# motorServoDriver.net
KiCad netlist of a schematic drawn in Altium Designer
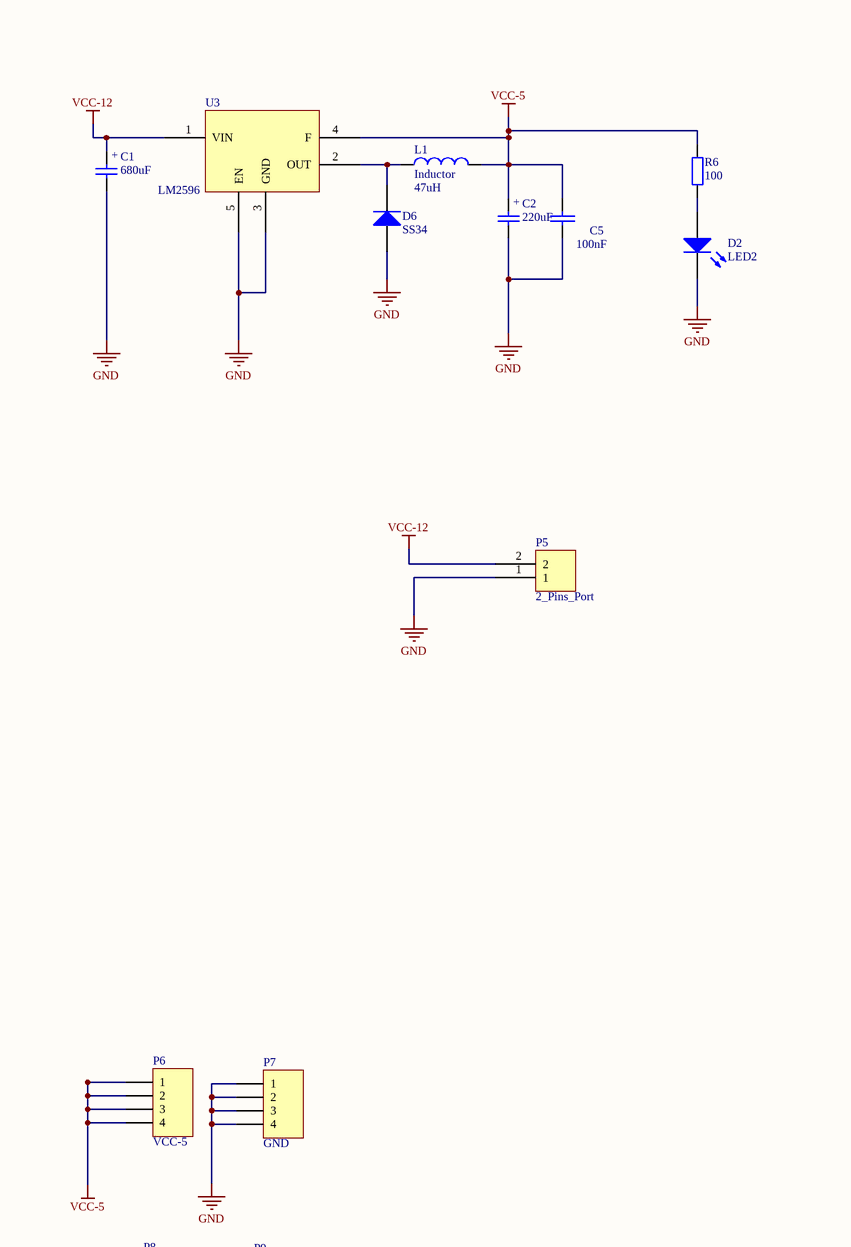
[diagram p0: motorServoDriver.SchDoc, top left]
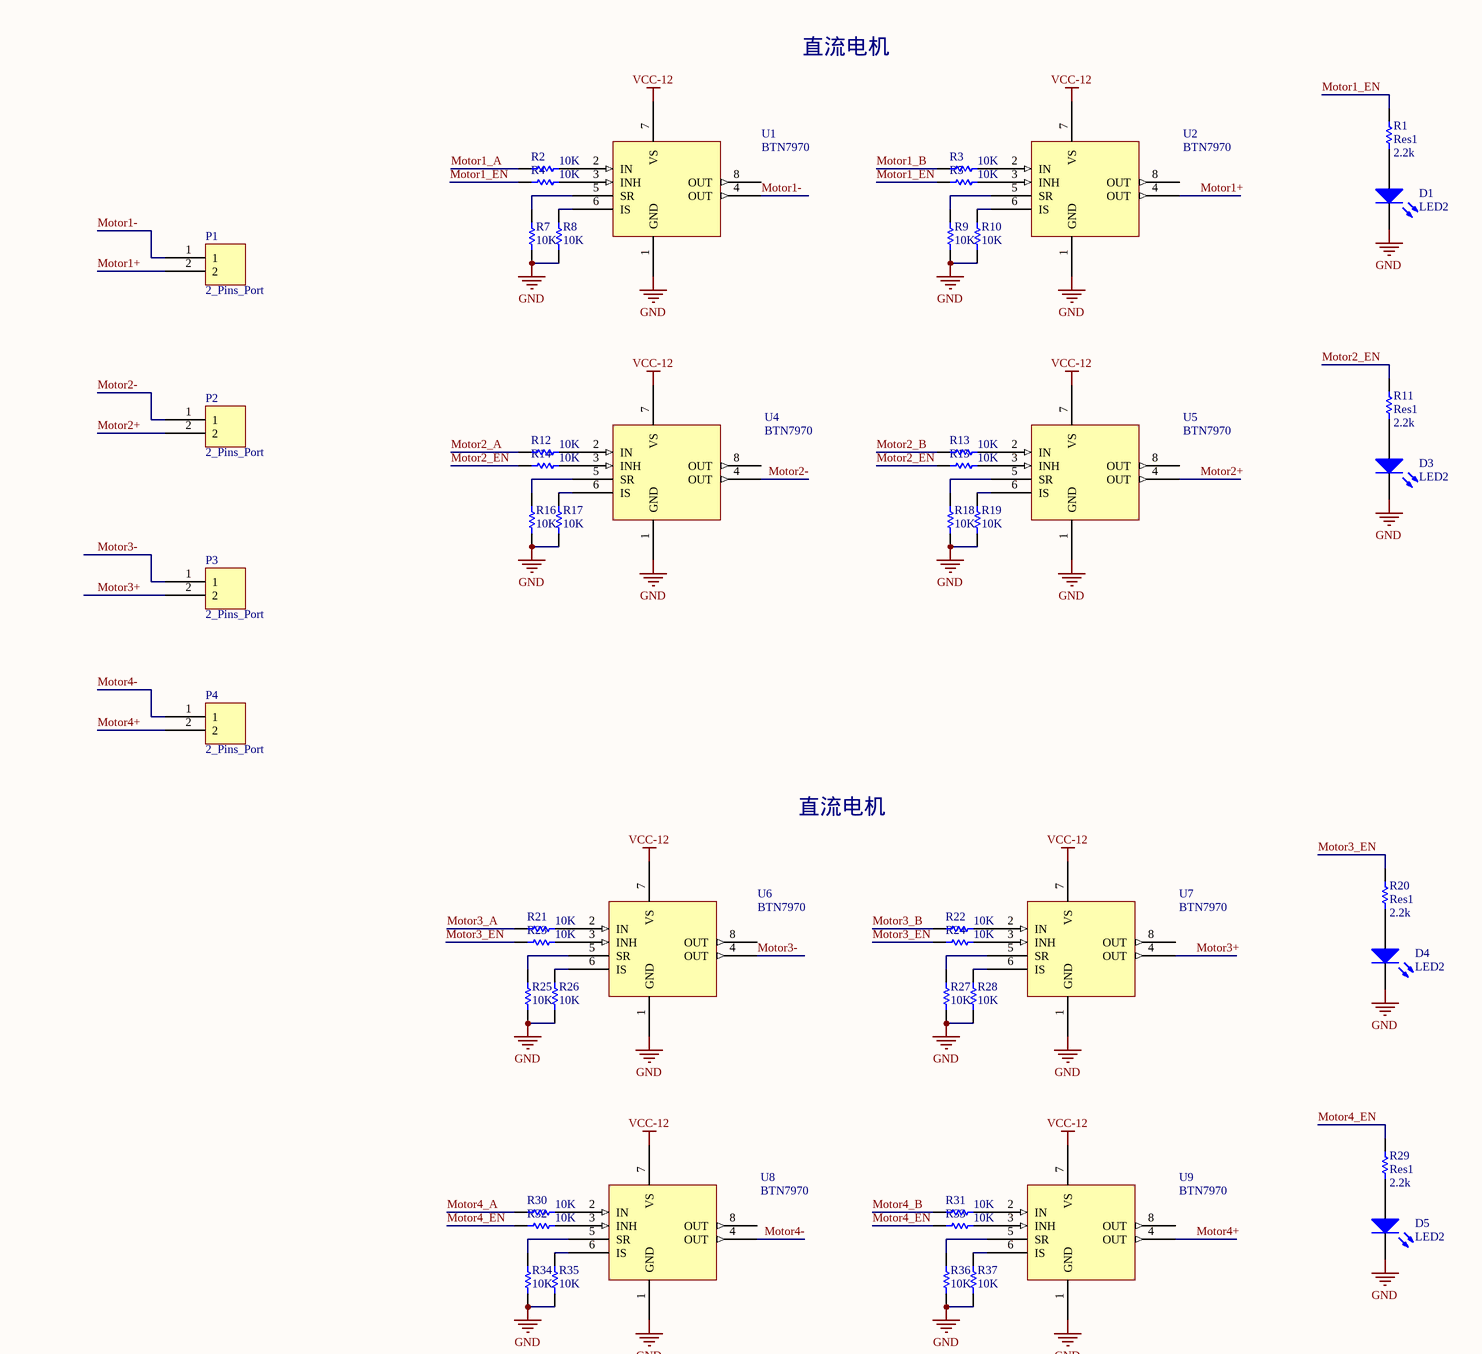
[diagram p1: motorServoDriver.SchDoc, top right]
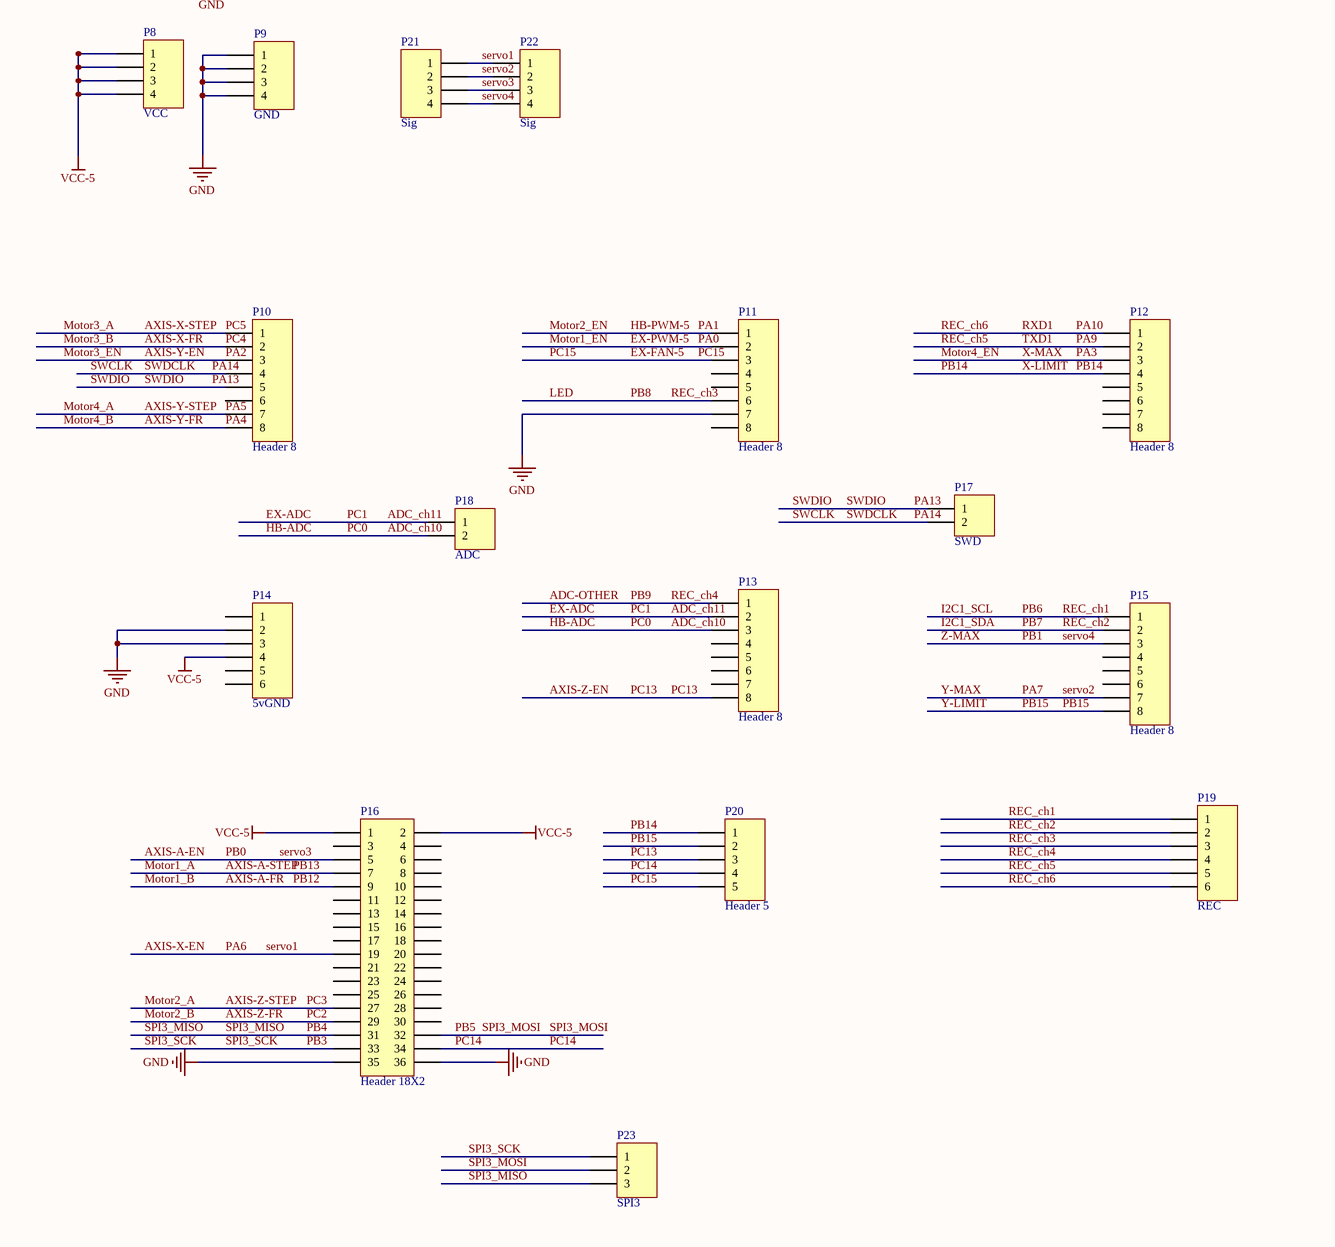
[diagram p2: motorServoDriver.SchDoc, bottom left]

(export (version "E")
  (design (tool "Eeschema 10.0.6"))
  (components
    (comp (ref "C1")
      (value "680uF")
      (footprint "CAP-7343")
      (description "贴片极性电容")
      (fields (field (name "Comment") "Cap"))
      (libsource (lib "SkyWorks2") (part "Cap Pol S"))
    )
    (comp (ref "C2")
      (value "220uF")
      (footprint "CAP-7343")
      (description "贴片极性电容")
      (fields (field (name "Comment") "Cap"))
      (libsource (lib "SkyWorks2") (part "Cap Pol S"))
    )
    (comp (ref "C5")
      (value "100nF")
      (footprint "CAP-0603")
      (description "贴片无极性电容")
      (fields (field (name "Comment") "cap smd"))
      (libsource (lib "SkyWorks2") (part "CAP"))
    )
    (comp (ref "D1")
      (value "LED2")
      (footprint "D2012[0805]")
      (description "Typical RED, GREEN, YELLOW, AMBER GaAs LED")
      (fields (field (name "PUBLISHER") "Altium Limited"))
      (libsource (lib "Miscellaneous Devices") (part "LED2"))
    )
    (comp (ref "D2")
      (value "LED2")
      (footprint "D2012[0805]")
      (description "Typical RED, GREEN, YELLOW, AMBER GaAs LED")
      (fields (field (name "PUBLISHER") "Altium Limited"))
      (libsource (lib "SkyWorks2") (part "LED2"))
    )
    (comp (ref "D3")
      (value "LED2")
      (footprint "D2012[0805]")
      (description "Typical RED, GREEN, YELLOW, AMBER GaAs LED")
      (fields (field (name "PUBLISHER") "Altium Limited"))
      (libsource (lib "Miscellaneous Devices") (part "LED2"))
    )
    (comp (ref "D4")
      (value "LED2")
      (footprint "D2012[0805]")
      (description "Typical RED, GREEN, YELLOW, AMBER GaAs LED")
      (fields (field (name "PUBLISHER") "Altium Limited"))
      (libsource (lib "Miscellaneous Devices") (part "LED2"))
    )
    (comp (ref "D5")
      (value "LED2")
      (footprint "D2012[0805]")
      (description "Typical RED, GREEN, YELLOW, AMBER GaAs LED")
      (fields (field (name "PUBLISHER") "Altium Limited"))
      (libsource (lib "Miscellaneous Devices") (part "LED2"))
    )
    (comp (ref "D6")
      (value "SS34")
      (footprint "LC-SMB(DO-214AA)_S3")
      (description "3 Amp General Purpose Rectifier")
      (fields (field (name "PUBLISHER") "Altium Limited"))
      (libsource (lib "Miscellaneous Devices") (part "Diode 1N5400"))
    )
    (comp (ref "L1")
      (value "Inductor")
      (footprint "Inductor1207")
      (fields (field (name "ALTIUM_VALUE") "47uH") (field (name "PUBLISHER") "Altium Limited"))
      (libsource (lib "Miscellaneous Devices") (part "Inductor"))
    )
    (comp (ref "P1")
      (value "2_Pins_Port")
      (footprint "WJ2EDGV-5.08-2P")
      (libsource (lib "transhcan") (part "2_Pins_Port"))
    )
    (comp (ref "P2")
      (value "2_Pins_Port")
      (footprint "WJ2EDGV-5.08-2P")
      (libsource (lib "transhcan") (part "2_Pins_Port"))
    )
    (comp (ref "P3")
      (value "2_Pins_Port")
      (footprint "WJ2EDGV-5.08-2P")
      (libsource (lib "transhcan") (part "2_Pins_Port"))
    )
    (comp (ref "P4")
      (value "2_Pins_Port")
      (footprint "WJ2EDGV-5.08-2P")
      (libsource (lib "transhcan") (part "2_Pins_Port"))
    )
    (comp (ref "P5")
      (value "2_Pins_Port")
      (footprint "WJ2EDGV-5.08-2P")
      (libsource (lib "") (part "2_Pins_Port_1"))
    )
    (comp (ref "P6")
      (value "VCC-5")
      (footprint "HDR1X4")
      (description "Header, 4-Pin")
      (fields (field (name "PUBLISHER") "Altium Limited"))
      (libsource (lib "Miscellaneous Connectors") (part "Header 4"))
    )
    (comp (ref "P7")
      (value "GND")
      (footprint "HDR1X4")
      (description "Header, 4-Pin")
      (fields (field (name "PUBLISHER") "Altium Limited"))
      (libsource (lib "Miscellaneous Connectors") (part "Header 4"))
    )
    (comp (ref "P8")
      (value "VCC")
      (footprint "HDR1X4")
      (description "Header, 4-Pin")
      (fields (field (name "PUBLISHER") "Altium Limited"))
      (libsource (lib "Miscellaneous Connectors") (part "Header 4"))
    )
    (comp (ref "P9")
      (value "GND")
      (footprint "HDR1X4")
      (description "Header, 4-Pin")
      (fields (field (name "PUBLISHER") "Altium Limited"))
      (libsource (lib "Miscellaneous Connectors") (part "Header 4"))
    )
    (comp (ref "P10")
      (value "Header 8")
      (footprint "HDR1X8")
      (description "Header, 8-Pin")
      (fields (field (name "PUBLISHER") "Altium Limited"))
      (libsource (lib "Miscellaneous Connectors") (part "Header 8"))
    )
    (comp (ref "P11")
      (value "Header 8")
      (footprint "HDR1X8")
      (description "Header, 8-Pin")
      (fields (field (name "PUBLISHER") "Altium Limited"))
      (libsource (lib "Miscellaneous Connectors") (part "Header 8"))
    )
    (comp (ref "P12")
      (value "Header 8")
      (footprint "HDR1X8")
      (description "Header, 8-Pin")
      (fields (field (name "PUBLISHER") "Altium Limited"))
      (libsource (lib "Miscellaneous Connectors") (part "Header 8"))
    )
    (comp (ref "P13")
      (value "Header 8")
      (footprint "HDR1X8")
      (description "Header, 8-Pin")
      (fields (field (name "PUBLISHER") "Altium Limited"))
      (libsource (lib "Miscellaneous Connectors") (part "Header 8"))
    )
    (comp (ref "P14")
      (value "5vGND")
      (footprint "HDR1x6")
      (description "Header, 6-Pin")
      (fields (field (name "PUBLISHER") "Altium Limited"))
      (libsource (lib "Miscellaneous Connectors") (part "Header 6"))
    )
    (comp (ref "P15")
      (value "Header 8")
      (footprint "HDR1X8")
      (description "Header, 8-Pin")
      (fields (field (name "PUBLISHER") "Altium Limited"))
      (libsource (lib "Miscellaneous Connectors") (part "Header 8"))
    )
    (comp (ref "P16")
      (value "Header 18X2")
      (footprint "HDR2X18")
      (description "Header, 18-Pin, Dual row")
      (fields (field (name "PUBLISHER") "Altium Limited"))
      (libsource (lib "Miscellaneous Connectors") (part "Header 18X2"))
    )
    (comp (ref "P17")
      (value "SWD")
      (footprint "HDR1X2")
      (description "Header, 2-Pin")
      (fields (field (name "PUBLISHER") "Altium Limited"))
      (libsource (lib "Miscellaneous Connectors") (part "Header 2"))
    )
    (comp (ref "P18")
      (value "ADC")
      (footprint "HDR1X2")
      (description "Header, 2-Pin")
      (fields (field (name "PUBLISHER") "Altium Limited"))
      (libsource (lib "Miscellaneous Connectors") (part "Header 2"))
    )
    (comp (ref "P19")
      (value "REC")
      (footprint "HDR1X6")
      (description "Header, 6-Pin")
      (fields (field (name "PUBLISHER") "Altium Limited"))
      (libsource (lib "Miscellaneous Connectors") (part "Header 6"))
    )
    (comp (ref "P20")
      (value "Header 5")
      (footprint "HDR1X5")
      (description "Header, 5-Pin")
      (fields (field (name "PUBLISHER") "Altium Limited"))
      (libsource (lib "Miscellaneous Connectors") (part "Header 5"))
    )
    (comp (ref "P21")
      (value "Sig")
      (footprint "HDR1X4")
      (description "Header, 4-Pin")
      (fields (field (name "PUBLISHER") "Altium Limited"))
      (libsource (lib "") (part "Header 4_1"))
    )
    (comp (ref "P22")
      (value "Sig")
      (footprint "HDR1X4")
      (description "Header, 4-Pin")
      (fields (field (name "PUBLISHER") "Altium Limited"))
      (libsource (lib "Miscellaneous Connectors") (part "Header 4"))
    )
    (comp (ref "P23")
      (value "SPI3")
      (footprint "HDR1X3")
      (description "Header, 3-Pin")
      (fields (field (name "PUBLISHER") "Altium Limited"))
      (libsource (lib "Miscellaneous Connectors") (part "Header 3"))
    )
    (comp (ref "R1")
      (value "Res1")
      (footprint "RES-0603")
      (description "Resistor")
      (fields (field (name "ALTIUM_VALUE") "2.2k") (field (name "PUBLISHER") "Altium Limited"))
      (libsource (lib "Miscellaneous Devices") (part "Res1"))
    )
    (comp (ref "R2")
      (value "10K")
      (footprint "RES-0603")
      (description "Resistor")
      (libsource (lib "MCU") (part "res1"))
    )
    (comp (ref "R3")
      (value "10K")
      (footprint "RES-0603")
      (description "Resistor")
      (libsource (lib "MCU") (part "res1"))
    )
    (comp (ref "R4")
      (value "10K")
      (footprint "RES-0603")
      (description "Resistor")
      (libsource (lib "MCU") (part "res1"))
    )
    (comp (ref "R5")
      (value "10K")
      (footprint "RES-0603")
      (description "Resistor")
      (libsource (lib "MCU") (part "res1"))
    )
    (comp (ref "R6")
      (value "100")
      (footprint "RES-0603")
      (fields (field (name "Comment") "RES1"))
      (libsource (lib "SkyWorks2") (part "RES1"))
    )
    (comp (ref "R7")
      (value "10K")
      (footprint "RES-0603")
      (description "Resistor")
      (libsource (lib "MCU") (part "res1"))
    )
    (comp (ref "R8")
      (value "10K")
      (footprint "RES-0603")
      (description "Resistor")
      (libsource (lib "MCU") (part "res1"))
    )
    (comp (ref "R9")
      (value "10K")
      (footprint "RES-0603")
      (description "Resistor")
      (libsource (lib "MCU") (part "res1"))
    )
    (comp (ref "R10")
      (value "10K")
      (footprint "RES-0603")
      (description "Resistor")
      (libsource (lib "MCU") (part "res1"))
    )
    (comp (ref "R11")
      (value "Res1")
      (footprint "RES-0603")
      (description "Resistor")
      (fields (field (name "ALTIUM_VALUE") "2.2k") (field (name "PUBLISHER") "Altium Limited"))
      (libsource (lib "Miscellaneous Devices") (part "Res1"))
    )
    (comp (ref "R12")
      (value "10K")
      (footprint "RES-0603")
      (description "Resistor")
      (libsource (lib "MCU") (part "res1"))
    )
    (comp (ref "R13")
      (value "10K")
      (footprint "RES-0603")
      (description "Resistor")
      (libsource (lib "MCU") (part "res1"))
    )
    (comp (ref "R14")
      (value "10K")
      (footprint "RES-0603")
      (description "Resistor")
      (libsource (lib "MCU") (part "res1"))
    )
    (comp (ref "R15")
      (value "10K")
      (footprint "RES-0603")
      (description "Resistor")
      (libsource (lib "MCU") (part "res1"))
    )
    (comp (ref "R16")
      (value "10K")
      (footprint "RES-0603")
      (description "Resistor")
      (libsource (lib "MCU") (part "res1"))
    )
    (comp (ref "R17")
      (value "10K")
      (footprint "RES-0603")
      (description "Resistor")
      (libsource (lib "MCU") (part "res1"))
    )
    (comp (ref "R18")
      (value "10K")
      (footprint "RES-0603")
      (description "Resistor")
      (libsource (lib "MCU") (part "res1"))
    )
    (comp (ref "R19")
      (value "10K")
      (footprint "RES-0603")
      (description "Resistor")
      (libsource (lib "MCU") (part "res1"))
    )
    (comp (ref "R20")
      (value "Res1")
      (footprint "RES-0603")
      (description "Resistor")
      (fields (field (name "ALTIUM_VALUE") "2.2k") (field (name "PUBLISHER") "Altium Limited"))
      (libsource (lib "Miscellaneous Devices") (part "Res1"))
    )
    (comp (ref "R21")
      (value "10K")
      (footprint "RES-0603")
      (description "Resistor")
      (libsource (lib "MCU") (part "res1"))
    )
    (comp (ref "R22")
      (value "10K")
      (footprint "RES-0603")
      (description "Resistor")
      (libsource (lib "MCU") (part "res1"))
    )
    (comp (ref "R23")
      (value "10K")
      (footprint "RES-0603")
      (description "Resistor")
      (libsource (lib "MCU") (part "res1"))
    )
    (comp (ref "R24")
      (value "10K")
      (footprint "RES-0603")
      (description "Resistor")
      (libsource (lib "MCU") (part "res1"))
    )
    (comp (ref "R25")
      (value "10K")
      (footprint "RES-0603")
      (description "Resistor")
      (libsource (lib "MCU") (part "res1"))
    )
    (comp (ref "R26")
      (value "10K")
      (footprint "RES-0603")
      (description "Resistor")
      (libsource (lib "MCU") (part "res1"))
    )
    (comp (ref "R27")
      (value "10K")
      (footprint "RES-0603")
      (description "Resistor")
      (libsource (lib "MCU") (part "res1"))
    )
    (comp (ref "R28")
      (value "10K")
      (footprint "RES-0603")
      (description "Resistor")
      (libsource (lib "MCU") (part "res1"))
    )
    (comp (ref "R29")
      (value "Res1")
      (footprint "RES-0603")
      (description "Resistor")
      (fields (field (name "ALTIUM_VALUE") "2.2k") (field (name "PUBLISHER") "Altium Limited"))
      (libsource (lib "Miscellaneous Devices") (part "Res1"))
    )
    (comp (ref "R30")
      (value "10K")
      (footprint "RES-0603")
      (description "Resistor")
      (libsource (lib "MCU") (part "res1"))
    )
    (comp (ref "R31")
      (value "10K")
      (footprint "RES-0603")
      (description "Resistor")
      (libsource (lib "MCU") (part "res1"))
    )
    (comp (ref "R32")
      (value "10K")
      (footprint "RES-0603")
      (description "Resistor")
      (libsource (lib "MCU") (part "res1"))
    )
    (comp (ref "R33")
      (value "10K")
      (footprint "RES-0603")
      (description "Resistor")
      (libsource (lib "MCU") (part "res1"))
    )
    (comp (ref "R34")
      (value "10K")
      (footprint "RES-0603")
      (description "Resistor")
      (libsource (lib "MCU") (part "res1"))
    )
    (comp (ref "R35")
      (value "10K")
      (footprint "RES-0603")
      (description "Resistor")
      (libsource (lib "MCU") (part "res1"))
    )
    (comp (ref "R36")
      (value "10K")
      (footprint "RES-0603")
      (description "Resistor")
      (libsource (lib "MCU") (part "res1"))
    )
    (comp (ref "R37")
      (value "10K")
      (footprint "RES-0603")
      (description "Resistor")
      (libsource (lib "MCU") (part "res1"))
    )
    (comp (ref "U1") (value "BTN7970") (footprint "BTN7970") (libsource (lib "transhcan") (part "BTN7970")))
    (comp (ref "U2") (value "BTN7970") (footprint "BTN7970") (libsource (lib "transhcan") (part "BTN7970")))
    (comp (ref "U3") (value "LM2596") (footprint "LC-TO-263-5") (libsource (lib "MLI") (part "LM2596")))
    (comp (ref "U4") (value "BTN7970") (footprint "BTN7970") (libsource (lib "transhcan") (part "BTN7970")))
    (comp (ref "U5") (value "BTN7970") (footprint "BTN7970") (libsource (lib "transhcan") (part "BTN7970")))
    (comp (ref "U6") (value "BTN7970") (footprint "BTN7970") (libsource (lib "transhcan") (part "BTN7970")))
    (comp (ref "U7") (value "BTN7970") (footprint "BTN7970") (libsource (lib "transhcan") (part "BTN7970")))
    (comp (ref "U8") (value "BTN7970") (footprint "BTN7970") (libsource (lib "transhcan") (part "BTN7970")))
    (comp (ref "U9") (value "BTN7970") (footprint "BTN7970") (libsource (lib "transhcan") (part "BTN7970")))
  )
  (nets
    (net (code "1") (name "/ADC-OTHER") (class "Default")
      (node (ref "P13") (pin "1") (pinfunction "1_1") (pintype "passive"))
      (node (ref "P19") (pin "4") (pinfunction "4_4") (pintype "passive"))
    )
    (net (code "2") (name "/ADC_ch10") (class "Default")
      (node (ref "P13") (pin "3") (pinfunction "3_3") (pintype "passive"))
      (node (ref "P18") (pin "2") (pinfunction "2_2") (pintype "passive"))
    )
    (net (code "3") (name "/ADC_ch11") (class "Default")
      (node (ref "P13") (pin "2") (pinfunction "2_2") (pintype "passive"))
      (node (ref "P18") (pin "1") (pinfunction "1_1") (pintype "passive"))
    )
    (net (code "4") (name "/AXIS-A-EN") (class "Default")
      (node (ref "P16") (pin "5") (pinfunction "5_5") (pintype "passive"))
      (node (ref "P21") (pin "3") (pinfunction "3_3") (pintype "passive"))
      (node (ref "P22") (pin "3") (pinfunction "3_3") (pintype "passive"))
    )
    (net (code "5") (name "/AXIS-A-FR") (class "Default")
      (node (ref "P16") (pin "9") (pinfunction "9_9") (pintype "passive"))
      (node (ref "R3") (pin "1") (pinfunction "1_1") (pintype "passive"))
    )
    (net (code "6") (name "/AXIS-A-STEP") (class "Default")
      (node (ref "P16") (pin "7") (pinfunction "7_7") (pintype "passive"))
      (node (ref "R2") (pin "1") (pinfunction "1_1") (pintype "passive"))
    )
    (net (code "7") (name "/AXIS-X-EN") (class "Default")
      (node (ref "P16") (pin "19") (pinfunction "19_19") (pintype "passive"))
      (node (ref "P21") (pin "1") (pinfunction "1_1") (pintype "passive"))
      (node (ref "P22") (pin "1") (pinfunction "1_1") (pintype "passive"))
    )
    (net (code "8") (name "/AXIS-X-FR") (class "Default")
      (node (ref "P10") (pin "2") (pinfunction "2_2") (pintype "passive"))
      (node (ref "R22") (pin "1") (pinfunction "1_1") (pintype "passive"))
    )
    (net (code "9") (name "/AXIS-X-STEP") (class "Default")
      (node (ref "P10") (pin "1") (pinfunction "1_1") (pintype "passive"))
      (node (ref "R21") (pin "1") (pinfunction "1_1") (pintype "passive"))
    )
    (net (code "10") (name "/AXIS-Y-EN") (class "Default")
      (node (ref "P10") (pin "3") (pinfunction "3_3") (pintype "passive"))
      (node (ref "R20") (pin "2") (pinfunction "2_2") (pintype "passive"))
      (node (ref "R23") (pin "1") (pinfunction "1_1") (pintype "passive"))
      (node (ref "R24") (pin "1") (pinfunction "1_1") (pintype "passive"))
    )
    (net (code "11") (name "/AXIS-Y-FR") (class "Default")
      (node (ref "P10") (pin "8") (pinfunction "8_8") (pintype "passive"))
      (node (ref "R31") (pin "1") (pinfunction "1_1") (pintype "passive"))
    )
    (net (code "12") (name "/AXIS-Y-STEP") (class "Default")
      (node (ref "P10") (pin "7") (pinfunction "7_7") (pintype "passive"))
      (node (ref "R30") (pin "1") (pinfunction "1_1") (pintype "passive"))
    )
    (net (code "13") (name "/AXIS-Z-EN") (class "Default")
      (node (ref "P13") (pin "8") (pinfunction "8_8") (pintype "passive"))
      (node (ref "P20") (pin "3") (pinfunction "3_3") (pintype "passive"))
    )
    (net (code "14") (name "/AXIS-Z-FR") (class "Default")
      (node (ref "P16") (pin "29") (pinfunction "29_29") (pintype "passive"))
      (node (ref "R13") (pin "1") (pinfunction "1_1") (pintype "passive"))
    )
    (net (code "15") (name "/AXIS-Z-STEP") (class "Default")
      (node (ref "P16") (pin "27") (pinfunction "27_27") (pintype "passive"))
      (node (ref "R12") (pin "1") (pinfunction "1_1") (pintype "passive"))
    )
    (net (code "16") (name "/EX-FAN-5") (class "Default")
      (node (ref "P11") (pin "3") (pinfunction "3_3") (pintype "passive"))
      (node (ref "P20") (pin "5") (pinfunction "5_5") (pintype "passive"))
    )
    (net (code "17") (name "/EX-PWM-5") (class "Default")
      (node (ref "P11") (pin "2") (pinfunction "2_2") (pintype "passive"))
      (node (ref "R1") (pin "2") (pinfunction "2_2") (pintype "passive"))
      (node (ref "R4") (pin "1") (pinfunction "1_1") (pintype "passive"))
      (node (ref "R5") (pin "1") (pinfunction "1_1") (pintype "passive"))
    )
    (net (code "18") (name "/HB-PWM-5") (class "Default")
      (node (ref "P11") (pin "1") (pinfunction "1_1") (pintype "passive"))
      (node (ref "R11") (pin "2") (pinfunction "2_2") (pintype "passive"))
      (node (ref "R14") (pin "1") (pinfunction "1_1") (pintype "passive"))
      (node (ref "R15") (pin "1") (pinfunction "1_1") (pintype "passive"))
    )
    (net (code "19") (name "/I2C1_SCL") (class "Default")
      (node (ref "P15") (pin "1") (pinfunction "1_1") (pintype "passive"))
      (node (ref "P19") (pin "1") (pinfunction "1_1") (pintype "passive"))
    )
    (net (code "20") (name "/I2C1_SDA") (class "Default")
      (node (ref "P15") (pin "2") (pinfunction "2_2") (pintype "passive"))
      (node (ref "P19") (pin "2") (pinfunction "2_2") (pintype "passive"))
    )
    (net (code "21") (name "/LED") (class "Default")
      (node (ref "P11") (pin "6") (pinfunction "6_6") (pintype "passive"))
      (node (ref "P19") (pin "3") (pinfunction "3_3") (pintype "passive"))
    )
    (net (code "22") (name "/Motor1+") (class "Default")
      (node (ref "P1") (pin "2") (pinfunction "2_2") (pintype "passive"))
      (node (ref "U2") (pin "4") (pinfunction "OUT_4") (pintype "output"))
    )
    (net (code "23") (name "/Motor1-") (class "Default")
      (node (ref "P1") (pin "1") (pinfunction "1_1") (pintype "passive"))
      (node (ref "U1") (pin "4") (pinfunction "OUT_4") (pintype "output"))
    )
    (net (code "24") (name "/Motor2+") (class "Default")
      (node (ref "P2") (pin "2") (pinfunction "2_2") (pintype "passive"))
      (node (ref "U5") (pin "4") (pinfunction "OUT_4") (pintype "output"))
    )
    (net (code "25") (name "/Motor2-") (class "Default")
      (node (ref "P2") (pin "1") (pinfunction "1_1") (pintype "passive"))
      (node (ref "U4") (pin "4") (pinfunction "OUT_4") (pintype "output"))
    )
    (net (code "26") (name "/Motor3+") (class "Default")
      (node (ref "P3") (pin "2") (pinfunction "2_2") (pintype "passive"))
      (node (ref "U7") (pin "4") (pinfunction "OUT_4") (pintype "output"))
    )
    (net (code "27") (name "/Motor3-") (class "Default")
      (node (ref "P3") (pin "1") (pinfunction "1_1") (pintype "passive"))
      (node (ref "U6") (pin "4") (pinfunction "OUT_4") (pintype "output"))
    )
    (net (code "28") (name "/Motor4+") (class "Default")
      (node (ref "P4") (pin "2") (pinfunction "2_2") (pintype "passive"))
      (node (ref "U9") (pin "4") (pinfunction "OUT_4") (pintype "output"))
    )
    (net (code "29") (name "/Motor4-") (class "Default")
      (node (ref "P4") (pin "1") (pinfunction "1_1") (pintype "passive"))
      (node (ref "U8") (pin "4") (pinfunction "OUT_4") (pintype "output"))
    )
    (net (code "30") (name "/Motor4_EN") (class "Default")
      (node (ref "P12") (pin "3") (pinfunction "3_3") (pintype "passive"))
      (node (ref "R29") (pin "2") (pinfunction "2_2") (pintype "passive"))
      (node (ref "R32") (pin "1") (pinfunction "1_1") (pintype "passive"))
      (node (ref "R33") (pin "1") (pinfunction "1_1") (pintype "passive"))
    )
    (net (code "31") (name "/PA7") (class "Default")
      (node (ref "P15") (pin "7") (pinfunction "7_7") (pintype "passive"))
      (node (ref "P21") (pin "2") (pinfunction "2_2") (pintype "passive"))
      (node (ref "P22") (pin "2") (pinfunction "2_2") (pintype "passive"))
    )
    (net (code "32") (name "/PA9") (class "Default")
      (node (ref "P12") (pin "2") (pinfunction "2_2") (pintype "passive"))
      (node (ref "P19") (pin "5") (pinfunction "5_5") (pintype "passive"))
    )
    (net (code "33") (name "/PA10") (class "Default")
      (node (ref "P12") (pin "1") (pinfunction "1_1") (pintype "passive"))
      (node (ref "P19") (pin "6") (pinfunction "6_6") (pintype "passive"))
    )
    (net (code "34") (name "/PA13") (class "Default")
      (node (ref "P10") (pin "5") (pinfunction "5_5") (pintype "passive"))
      (node (ref "P17") (pin "1") (pinfunction "1_1") (pintype "passive"))
    )
    (net (code "35") (name "/PA14") (class "Default")
      (node (ref "P10") (pin "4") (pinfunction "4_4") (pintype "passive"))
      (node (ref "P17") (pin "2") (pinfunction "2_2") (pintype "passive"))
    )
    (net (code "36") (name "/PB1") (class "Default")
      (node (ref "P15") (pin "3") (pinfunction "3_3") (pintype "passive"))
      (node (ref "P21") (pin "4") (pinfunction "4_4") (pintype "passive"))
      (node (ref "P22") (pin "4") (pinfunction "4_4") (pintype "passive"))
    )
    (net (code "37") (name "/PB3") (class "Default")
      (node (ref "P16") (pin "33") (pinfunction "33_33") (pintype "passive"))
      (node (ref "P23") (pin "1") (pinfunction "1_1") (pintype "passive"))
    )
    (net (code "38") (name "/PB4") (class "Default")
      (node (ref "P16") (pin "31") (pinfunction "31_31") (pintype "passive"))
      (node (ref "P23") (pin "3") (pinfunction "3_3") (pintype "passive"))
    )
    (net (code "39") (name "/PB5") (class "Default")
      (node (ref "P16") (pin "32") (pinfunction "32_32") (pintype "passive"))
      (node (ref "P23") (pin "2") (pinfunction "2_2") (pintype "passive"))
    )
    (net (code "40") (name "/PB14") (class "Default")
      (node (ref "P12") (pin "4") (pinfunction "4_4") (pintype "passive"))
      (node (ref "P20") (pin "1") (pinfunction "1_1") (pintype "passive"))
    )
    (net (code "41") (name "/PB15") (class "Default")
      (node (ref "P15") (pin "8") (pinfunction "8_8") (pintype "passive"))
      (node (ref "P20") (pin "2") (pinfunction "2_2") (pintype "passive"))
    )
    (net (code "42") (name "/PC14") (class "Default")
      (node (ref "P16") (pin "34") (pinfunction "34_34") (pintype "passive"))
      (node (ref "P20") (pin "4") (pinfunction "4_4") (pintype "passive"))
    )
    (net (code "43") (name "GND") (class "Default")
      (node (ref "C1") (pin "2") (pinfunction "-_2") (pintype "passive"))
      (node (ref "C2") (pin "2") (pinfunction "-_2") (pintype "passive"))
      (node (ref "C5") (pin "2") (pinfunction "2_2") (pintype "passive"))
      (node (ref "D1") (pin "2") (pinfunction "K_2") (pintype "passive"))
      (node (ref "D2") (pin "2") (pinfunction "K_2") (pintype "passive"))
      (node (ref "D3") (pin "2") (pinfunction "K_2") (pintype "passive"))
      (node (ref "D4") (pin "2") (pinfunction "K_2") (pintype "passive"))
      (node (ref "D5") (pin "2") (pinfunction "K_2") (pintype "passive"))
      (node (ref "D6") (pin "1") (pinfunction "A_1") (pintype "passive"))
      (node (ref "P11") (pin "7") (pinfunction "7_7") (pintype "passive"))
      (node (ref "P14") (pin "2") (pinfunction "2_2") (pintype "passive"))
      (node (ref "P14") (pin "3") (pinfunction "3_3") (pintype "passive"))
      (node (ref "P16") (pin "35") (pinfunction "35_35") (pintype "passive"))
      (node (ref "P16") (pin "36") (pinfunction "36_36") (pintype "passive"))
      (node (ref "P5") (pin "1") (pinfunction "1_1") (pintype "passive"))
      (node (ref "P7") (pin "1") (pinfunction "1_1") (pintype "passive"))
      (node (ref "P7") (pin "2") (pinfunction "2_2") (pintype "passive"))
      (node (ref "P7") (pin "3") (pinfunction "3_3") (pintype "passive"))
      (node (ref "P7") (pin "4") (pinfunction "4_4") (pintype "passive"))
      (node (ref "P9") (pin "1") (pinfunction "1_1") (pintype "passive"))
      (node (ref "P9") (pin "2") (pinfunction "2_2") (pintype "passive"))
      (node (ref "P9") (pin "3") (pinfunction "3_3") (pintype "passive"))
      (node (ref "P9") (pin "4") (pinfunction "4_4") (pintype "passive"))
      (node (ref "R10") (pin "1") (pinfunction "1_1") (pintype "passive"))
      (node (ref "R16") (pin "1") (pinfunction "1_1") (pintype "passive"))
      (node (ref "R17") (pin "1") (pinfunction "1_1") (pintype "passive"))
      (node (ref "R18") (pin "1") (pinfunction "1_1") (pintype "passive"))
      (node (ref "R19") (pin "1") (pinfunction "1_1") (pintype "passive"))
      (node (ref "R25") (pin "1") (pinfunction "1_1") (pintype "passive"))
      (node (ref "R26") (pin "1") (pinfunction "1_1") (pintype "passive"))
      (node (ref "R27") (pin "1") (pinfunction "1_1") (pintype "passive"))
      (node (ref "R28") (pin "1") (pinfunction "1_1") (pintype "passive"))
      (node (ref "R34") (pin "1") (pinfunction "1_1") (pintype "passive"))
      (node (ref "R35") (pin "1") (pinfunction "1_1") (pintype "passive"))
      (node (ref "R36") (pin "1") (pinfunction "1_1") (pintype "passive"))
      (node (ref "R37") (pin "1") (pinfunction "1_1") (pintype "passive"))
      (node (ref "R7") (pin "1") (pinfunction "1_1") (pintype "passive"))
      (node (ref "R8") (pin "1") (pinfunction "1_1") (pintype "passive"))
      (node (ref "R9") (pin "1") (pinfunction "1_1") (pintype "passive"))
      (node (ref "U1") (pin "1") (pinfunction "GND_1") (pintype "passive"))
      (node (ref "U2") (pin "1") (pinfunction "GND_1") (pintype "passive"))
      (node (ref "U3") (pin "3") (pinfunction "GND_3") (pintype "passive"))
      (node (ref "U3") (pin "5") (pinfunction "EN_5") (pintype "passive"))
      (node (ref "U4") (pin "1") (pinfunction "GND_1") (pintype "passive"))
      (node (ref "U5") (pin "1") (pinfunction "GND_1") (pintype "passive"))
      (node (ref "U6") (pin "1") (pinfunction "GND_1") (pintype "passive"))
      (node (ref "U7") (pin "1") (pinfunction "GND_1") (pintype "passive"))
      (node (ref "U8") (pin "1") (pinfunction "GND_1") (pintype "passive"))
      (node (ref "U9") (pin "1") (pinfunction "GND_1") (pintype "passive"))
    )
    (net (code "44") (name "Net-(D1-A)") (class "Default")
      (node (ref "D1") (pin "1") (pinfunction "A_1") (pintype "passive"))
      (node (ref "R1") (pin "1") (pinfunction "1_1") (pintype "passive"))
    )
    (net (code "45") (name "Net-(D2-A)") (class "Default")
      (node (ref "D2") (pin "1") (pinfunction "A_1") (pintype "passive"))
      (node (ref "R6") (pin "1") (pinfunction "1_1") (pintype "passive"))
    )
    (net (code "46") (name "Net-(D3-A)") (class "Default")
      (node (ref "D3") (pin "1") (pinfunction "A_1") (pintype "passive"))
      (node (ref "R11") (pin "1") (pinfunction "1_1") (pintype "passive"))
    )
    (net (code "47") (name "Net-(D4-A)") (class "Default")
      (node (ref "D4") (pin "1") (pinfunction "A_1") (pintype "passive"))
      (node (ref "R20") (pin "1") (pinfunction "1_1") (pintype "passive"))
    )
    (net (code "48") (name "Net-(D5-A)") (class "Default")
      (node (ref "D5") (pin "1") (pinfunction "A_1") (pintype "passive"))
      (node (ref "R29") (pin "1") (pinfunction "1_1") (pintype "passive"))
    )
    (net (code "49") (name "Net-(D6-K)") (class "Default")
      (node (ref "D6") (pin "2") (pinfunction "K_2") (pintype "passive"))
      (node (ref "L1") (pin "1") (pinfunction "1_1") (pintype "passive"))
      (node (ref "U3") (pin "2") (pinfunction "OUT_2") (pintype "passive"))
    )
    (net (code "50") (name "Net-(U1-IN)") (class "Default")
      (node (ref "R2") (pin "2") (pinfunction "2_2") (pintype "passive"))
      (node (ref "U1") (pin "2") (pinfunction "IN_2") (pintype "input"))
    )
    (net (code "51") (name "Net-(U1-INH)") (class "Default")
      (node (ref "R4") (pin "2") (pinfunction "2_2") (pintype "passive"))
      (node (ref "U1") (pin "3") (pinfunction "INH_3") (pintype "input"))
    )
    (net (code "52") (name "Net-(U1-IS)") (class "Default")
      (node (ref "R8") (pin "2") (pinfunction "2_2") (pintype "passive"))
      (node (ref "U1") (pin "6") (pinfunction "IS_6") (pintype "passive"))
    )
    (net (code "53") (name "Net-(U1-SR)") (class "Default")
      (node (ref "R7") (pin "2") (pinfunction "2_2") (pintype "passive"))
      (node (ref "U1") (pin "5") (pinfunction "SR_5") (pintype "passive"))
    )
    (net (code "54") (name "Net-(U2-IN)") (class "Default")
      (node (ref "R3") (pin "2") (pinfunction "2_2") (pintype "passive"))
      (node (ref "U2") (pin "2") (pinfunction "IN_2") (pintype "input"))
    )
    (net (code "55") (name "Net-(U2-INH)") (class "Default")
      (node (ref "R5") (pin "2") (pinfunction "2_2") (pintype "passive"))
      (node (ref "U2") (pin "3") (pinfunction "INH_3") (pintype "input"))
    )
    (net (code "56") (name "Net-(U2-IS)") (class "Default")
      (node (ref "R10") (pin "2") (pinfunction "2_2") (pintype "passive"))
      (node (ref "U2") (pin "6") (pinfunction "IS_6") (pintype "passive"))
    )
    (net (code "57") (name "Net-(U2-SR)") (class "Default")
      (node (ref "R9") (pin "2") (pinfunction "2_2") (pintype "passive"))
      (node (ref "U2") (pin "5") (pinfunction "SR_5") (pintype "passive"))
    )
    (net (code "58") (name "Net-(U4-IN)") (class "Default")
      (node (ref "R12") (pin "2") (pinfunction "2_2") (pintype "passive"))
      (node (ref "U4") (pin "2") (pinfunction "IN_2") (pintype "input"))
    )
    (net (code "59") (name "Net-(U4-INH)") (class "Default")
      (node (ref "R14") (pin "2") (pinfunction "2_2") (pintype "passive"))
      (node (ref "U4") (pin "3") (pinfunction "INH_3") (pintype "input"))
    )
    (net (code "60") (name "Net-(U4-IS)") (class "Default")
      (node (ref "R17") (pin "2") (pinfunction "2_2") (pintype "passive"))
      (node (ref "U4") (pin "6") (pinfunction "IS_6") (pintype "passive"))
    )
    (net (code "61") (name "Net-(U4-SR)") (class "Default")
      (node (ref "R16") (pin "2") (pinfunction "2_2") (pintype "passive"))
      (node (ref "U4") (pin "5") (pinfunction "SR_5") (pintype "passive"))
    )
    (net (code "62") (name "Net-(U5-IN)") (class "Default")
      (node (ref "R13") (pin "2") (pinfunction "2_2") (pintype "passive"))
      (node (ref "U5") (pin "2") (pinfunction "IN_2") (pintype "input"))
    )
    (net (code "63") (name "Net-(U5-INH)") (class "Default")
      (node (ref "R15") (pin "2") (pinfunction "2_2") (pintype "passive"))
      (node (ref "U5") (pin "3") (pinfunction "INH_3") (pintype "input"))
    )
    (net (code "64") (name "Net-(U5-IS)") (class "Default")
      (node (ref "R19") (pin "2") (pinfunction "2_2") (pintype "passive"))
      (node (ref "U5") (pin "6") (pinfunction "IS_6") (pintype "passive"))
    )
    (net (code "65") (name "Net-(U5-SR)") (class "Default")
      (node (ref "R18") (pin "2") (pinfunction "2_2") (pintype "passive"))
      (node (ref "U5") (pin "5") (pinfunction "SR_5") (pintype "passive"))
    )
    (net (code "66") (name "Net-(U6-IN)") (class "Default")
      (node (ref "R21") (pin "2") (pinfunction "2_2") (pintype "passive"))
      (node (ref "U6") (pin "2") (pinfunction "IN_2") (pintype "input"))
    )
    (net (code "67") (name "Net-(U6-INH)") (class "Default")
      (node (ref "R23") (pin "2") (pinfunction "2_2") (pintype "passive"))
      (node (ref "U6") (pin "3") (pinfunction "INH_3") (pintype "input"))
    )
    (net (code "68") (name "Net-(U6-IS)") (class "Default")
      (node (ref "R26") (pin "2") (pinfunction "2_2") (pintype "passive"))
      (node (ref "U6") (pin "6") (pinfunction "IS_6") (pintype "passive"))
    )
    (net (code "69") (name "Net-(U6-SR)") (class "Default")
      (node (ref "R25") (pin "2") (pinfunction "2_2") (pintype "passive"))
      (node (ref "U6") (pin "5") (pinfunction "SR_5") (pintype "passive"))
    )
    (net (code "70") (name "Net-(U7-IN)") (class "Default")
      (node (ref "R22") (pin "2") (pinfunction "2_2") (pintype "passive"))
      (node (ref "U7") (pin "2") (pinfunction "IN_2") (pintype "input"))
    )
    (net (code "71") (name "Net-(U7-INH)") (class "Default")
      (node (ref "R24") (pin "2") (pinfunction "2_2") (pintype "passive"))
      (node (ref "U7") (pin "3") (pinfunction "INH_3") (pintype "input"))
    )
    (net (code "72") (name "Net-(U7-IS)") (class "Default")
      (node (ref "R28") (pin "2") (pinfunction "2_2") (pintype "passive"))
      (node (ref "U7") (pin "6") (pinfunction "IS_6") (pintype "passive"))
    )
    (net (code "73") (name "Net-(U7-SR)") (class "Default")
      (node (ref "R27") (pin "2") (pinfunction "2_2") (pintype "passive"))
      (node (ref "U7") (pin "5") (pinfunction "SR_5") (pintype "passive"))
    )
    (net (code "74") (name "Net-(U8-IN)") (class "Default")
      (node (ref "R30") (pin "2") (pinfunction "2_2") (pintype "passive"))
      (node (ref "U8") (pin "2") (pinfunction "IN_2") (pintype "input"))
    )
    (net (code "75") (name "Net-(U8-INH)") (class "Default")
      (node (ref "R32") (pin "2") (pinfunction "2_2") (pintype "passive"))
      (node (ref "U8") (pin "3") (pinfunction "INH_3") (pintype "input"))
    )
    (net (code "76") (name "Net-(U8-IS)") (class "Default")
      (node (ref "R35") (pin "2") (pinfunction "2_2") (pintype "passive"))
      (node (ref "U8") (pin "6") (pinfunction "IS_6") (pintype "passive"))
    )
    (net (code "77") (name "Net-(U8-SR)") (class "Default")
      (node (ref "R34") (pin "2") (pinfunction "2_2") (pintype "passive"))
      (node (ref "U8") (pin "5") (pinfunction "SR_5") (pintype "passive"))
    )
    (net (code "78") (name "Net-(U9-IN)") (class "Default")
      (node (ref "R31") (pin "2") (pinfunction "2_2") (pintype "passive"))
      (node (ref "U9") (pin "2") (pinfunction "IN_2") (pintype "input"))
    )
    (net (code "79") (name "Net-(U9-INH)") (class "Default")
      (node (ref "R33") (pin "2") (pinfunction "2_2") (pintype "passive"))
      (node (ref "U9") (pin "3") (pinfunction "INH_3") (pintype "input"))
    )
    (net (code "80") (name "Net-(U9-IS)") (class "Default")
      (node (ref "R37") (pin "2") (pinfunction "2_2") (pintype "passive"))
      (node (ref "U9") (pin "6") (pinfunction "IS_6") (pintype "passive"))
    )
    (net (code "81") (name "Net-(U9-SR)") (class "Default")
      (node (ref "R36") (pin "2") (pinfunction "2_2") (pintype "passive"))
      (node (ref "U9") (pin "5") (pinfunction "SR_5") (pintype "passive"))
    )
    (net (code "82") (name "VCC-5") (class "Default")
      (node (ref "C2") (pin "1") (pinfunction "+_1") (pintype "passive"))
      (node (ref "C5") (pin "1") (pinfunction "1_1") (pintype "passive"))
      (node (ref "L1") (pin "2") (pinfunction "2_2") (pintype "passive"))
      (node (ref "P14") (pin "4") (pinfunction "4_4") (pintype "passive"))
      (node (ref "P16") (pin "1") (pinfunction "1_1") (pintype "passive"))
      (node (ref "P16") (pin "2") (pinfunction "2_2") (pintype "passive"))
      (node (ref "P6") (pin "1") (pinfunction "1_1") (pintype "passive"))
      (node (ref "P6") (pin "2") (pinfunction "2_2") (pintype "passive"))
      (node (ref "P6") (pin "3") (pinfunction "3_3") (pintype "passive"))
      (node (ref "P6") (pin "4") (pinfunction "4_4") (pintype "passive"))
      (node (ref "P8") (pin "1") (pinfunction "1_1") (pintype "passive"))
      (node (ref "P8") (pin "2") (pinfunction "2_2") (pintype "passive"))
      (node (ref "P8") (pin "3") (pinfunction "3_3") (pintype "passive"))
      (node (ref "P8") (pin "4") (pinfunction "4_4") (pintype "passive"))
      (node (ref "R6") (pin "2") (pinfunction "2_2") (pintype "passive"))
      (node (ref "U3") (pin "4") (pinfunction "F_4") (pintype "passive"))
    )
    (net (code "83") (name "VCC-12") (class "Default")
      (node (ref "C1") (pin "1") (pinfunction "+_1") (pintype "passive"))
      (node (ref "P5") (pin "2") (pinfunction "2_2") (pintype "passive"))
      (node (ref "U1") (pin "7") (pinfunction "VS_7") (pintype "passive"))
      (node (ref "U2") (pin "7") (pinfunction "VS_7") (pintype "passive"))
      (node (ref "U3") (pin "1") (pinfunction "VIN_1") (pintype "passive"))
      (node (ref "U4") (pin "7") (pinfunction "VS_7") (pintype "passive"))
      (node (ref "U5") (pin "7") (pinfunction "VS_7") (pintype "passive"))
      (node (ref "U6") (pin "7") (pinfunction "VS_7") (pintype "passive"))
      (node (ref "U7") (pin "7") (pinfunction "VS_7") (pintype "passive"))
      (node (ref "U8") (pin "7") (pinfunction "VS_7") (pintype "passive"))
      (node (ref "U9") (pin "7") (pinfunction "VS_7") (pintype "passive"))
    )
    (net (code "84") (name "unconnected-(P10-Pad6)") (class "Default")
      (node (ref "P10") (pin "6") (pinfunction "6_6") (pintype "passive"))
    )
    (net (code "85") (name "unconnected-(P11-Pad4)") (class "Default")
      (node (ref "P11") (pin "4") (pinfunction "4_4") (pintype "passive"))
    )
    (net (code "86") (name "unconnected-(P11-Pad5)") (class "Default")
      (node (ref "P11") (pin "5") (pinfunction "5_5") (pintype "passive"))
    )
    (net (code "87") (name "unconnected-(P11-Pad8)") (class "Default")
      (node (ref "P11") (pin "8") (pinfunction "8_8") (pintype "passive"))
    )
    (net (code "88") (name "unconnected-(P12-Pad5)") (class "Default")
      (node (ref "P12") (pin "5") (pinfunction "5_5") (pintype "passive"))
    )
    (net (code "89") (name "unconnected-(P12-Pad6)") (class "Default")
      (node (ref "P12") (pin "6") (pinfunction "6_6") (pintype "passive"))
    )
    (net (code "90") (name "unconnected-(P12-Pad7)") (class "Default")
      (node (ref "P12") (pin "7") (pinfunction "7_7") (pintype "passive"))
    )
    (net (code "91") (name "unconnected-(P12-Pad8)") (class "Default")
      (node (ref "P12") (pin "8") (pinfunction "8_8") (pintype "passive"))
    )
    (net (code "92") (name "unconnected-(P13-Pad4)") (class "Default")
      (node (ref "P13") (pin "4") (pinfunction "4_4") (pintype "passive"))
    )
    (net (code "93") (name "unconnected-(P13-Pad5)") (class "Default")
      (node (ref "P13") (pin "5") (pinfunction "5_5") (pintype "passive"))
    )
    (net (code "94") (name "unconnected-(P13-Pad6)") (class "Default")
      (node (ref "P13") (pin "6") (pinfunction "6_6") (pintype "passive"))
    )
    (net (code "95") (name "unconnected-(P13-Pad7)") (class "Default")
      (node (ref "P13") (pin "7") (pinfunction "7_7") (pintype "passive"))
    )
    (net (code "96") (name "unconnected-(P14-Pad1)") (class "Default")
      (node (ref "P14") (pin "1") (pinfunction "1_1") (pintype "passive"))
    )
    (net (code "97") (name "unconnected-(P14-Pad5)") (class "Default")
      (node (ref "P14") (pin "5") (pinfunction "5_5") (pintype "passive"))
    )
    (net (code "98") (name "unconnected-(P14-Pad6)") (class "Default")
      (node (ref "P14") (pin "6") (pinfunction "6_6") (pintype "passive"))
    )
    (net (code "99") (name "unconnected-(P15-Pad4)") (class "Default")
      (node (ref "P15") (pin "4") (pinfunction "4_4") (pintype "passive"))
    )
    (net (code "100") (name "unconnected-(P15-Pad5)") (class "Default")
      (node (ref "P15") (pin "5") (pinfunction "5_5") (pintype "passive"))
    )
    (net (code "101") (name "unconnected-(P15-Pad6)") (class "Default")
      (node (ref "P15") (pin "6") (pinfunction "6_6") (pintype "passive"))
    )
    (net (code "102") (name "unconnected-(P16-Pad3)") (class "Default")
      (node (ref "P16") (pin "3") (pinfunction "3_3") (pintype "passive"))
    )
    (net (code "103") (name "unconnected-(P16-Pad4)") (class "Default")
      (node (ref "P16") (pin "4") (pinfunction "4_4") (pintype "passive"))
    )
    (net (code "104") (name "unconnected-(P16-Pad6)") (class "Default")
      (node (ref "P16") (pin "6") (pinfunction "6_6") (pintype "passive"))
    )
    (net (code "105") (name "unconnected-(P16-Pad8)") (class "Default")
      (node (ref "P16") (pin "8") (pinfunction "8_8") (pintype "passive"))
    )
    (net (code "106") (name "unconnected-(P16-Pad10)") (class "Default")
      (node (ref "P16") (pin "10") (pinfunction "10_10") (pintype "passive"))
    )
    (net (code "107") (name "unconnected-(P16-Pad11)") (class "Default")
      (node (ref "P16") (pin "11") (pinfunction "11_11") (pintype "passive"))
    )
    (net (code "108") (name "unconnected-(P16-Pad12)") (class "Default")
      (node (ref "P16") (pin "12") (pinfunction "12_12") (pintype "passive"))
    )
    (net (code "109") (name "unconnected-(P16-Pad13)") (class "Default")
      (node (ref "P16") (pin "13") (pinfunction "13_13") (pintype "passive"))
    )
    (net (code "110") (name "unconnected-(P16-Pad14)") (class "Default")
      (node (ref "P16") (pin "14") (pinfunction "14_14") (pintype "passive"))
    )
    (net (code "111") (name "unconnected-(P16-Pad15)") (class "Default")
      (node (ref "P16") (pin "15") (pinfunction "15_15") (pintype "passive"))
    )
    (net (code "112") (name "unconnected-(P16-Pad16)") (class "Default")
      (node (ref "P16") (pin "16") (pinfunction "16_16") (pintype "passive"))
    )
    (net (code "113") (name "unconnected-(P16-Pad17)") (class "Default")
      (node (ref "P16") (pin "17") (pinfunction "17_17") (pintype "passive"))
    )
    (net (code "114") (name "unconnected-(P16-Pad18)") (class "Default")
      (node (ref "P16") (pin "18") (pinfunction "18_18") (pintype "passive"))
    )
    (net (code "115") (name "unconnected-(P16-Pad20)") (class "Default")
      (node (ref "P16") (pin "20") (pinfunction "20_20") (pintype "passive"))
    )
    (net (code "116") (name "unconnected-(P16-Pad21)") (class "Default")
      (node (ref "P16") (pin "21") (pinfunction "21_21") (pintype "passive"))
    )
    (net (code "117") (name "unconnected-(P16-Pad22)") (class "Default")
      (node (ref "P16") (pin "22") (pinfunction "22_22") (pintype "passive"))
    )
    (net (code "118") (name "unconnected-(P16-Pad23)") (class "Default")
      (node (ref "P16") (pin "23") (pinfunction "23_23") (pintype "passive"))
    )
    (net (code "119") (name "unconnected-(P16-Pad24)") (class "Default")
      (node (ref "P16") (pin "24") (pinfunction "24_24") (pintype "passive"))
    )
    (net (code "120") (name "unconnected-(P16-Pad25)") (class "Default")
      (node (ref "P16") (pin "25") (pinfunction "25_25") (pintype "passive"))
    )
    (net (code "121") (name "unconnected-(P16-Pad26)") (class "Default")
      (node (ref "P16") (pin "26") (pinfunction "26_26") (pintype "passive"))
    )
    (net (code "122") (name "unconnected-(P16-Pad28)") (class "Default")
      (node (ref "P16") (pin "28") (pinfunction "28_28") (pintype "passive"))
    )
    (net (code "123") (name "unconnected-(P16-Pad30)") (class "Default")
      (node (ref "P16") (pin "30") (pinfunction "30_30") (pintype "passive"))
    )
    (net (code "124") (name "unconnected-(U1-OUT-Pad8)") (class "Default")
      (node (ref "U1") (pin "8") (pinfunction "OUT_8") (pintype "output"))
    )
    (net (code "125") (name "unconnected-(U2-OUT-Pad8)") (class "Default")
      (node (ref "U2") (pin "8") (pinfunction "OUT_8") (pintype "output"))
    )
    (net (code "126") (name "unconnected-(U4-OUT-Pad8)") (class "Default")
      (node (ref "U4") (pin "8") (pinfunction "OUT_8") (pintype "output"))
    )
    (net (code "127") (name "unconnected-(U5-OUT-Pad8)") (class "Default")
      (node (ref "U5") (pin "8") (pinfunction "OUT_8") (pintype "output"))
    )
    (net (code "128") (name "unconnected-(U6-OUT-Pad8)") (class "Default")
      (node (ref "U6") (pin "8") (pinfunction "OUT_8") (pintype "output"))
    )
    (net (code "129") (name "unconnected-(U7-OUT-Pad8)") (class "Default")
      (node (ref "U7") (pin "8") (pinfunction "OUT_8") (pintype "output"))
    )
    (net (code "130") (name "unconnected-(U8-OUT-Pad8)") (class "Default")
      (node (ref "U8") (pin "8") (pinfunction "OUT_8") (pintype "output"))
    )
    (net (code "131") (name "unconnected-(U9-OUT-Pad8)") (class "Default")
      (node (ref "U9") (pin "8") (pinfunction "OUT_8") (pintype "output"))
    )
  )
)
